# Schematic1.net
KiCad netlist of a schematic drawn in EasyEDA Pro
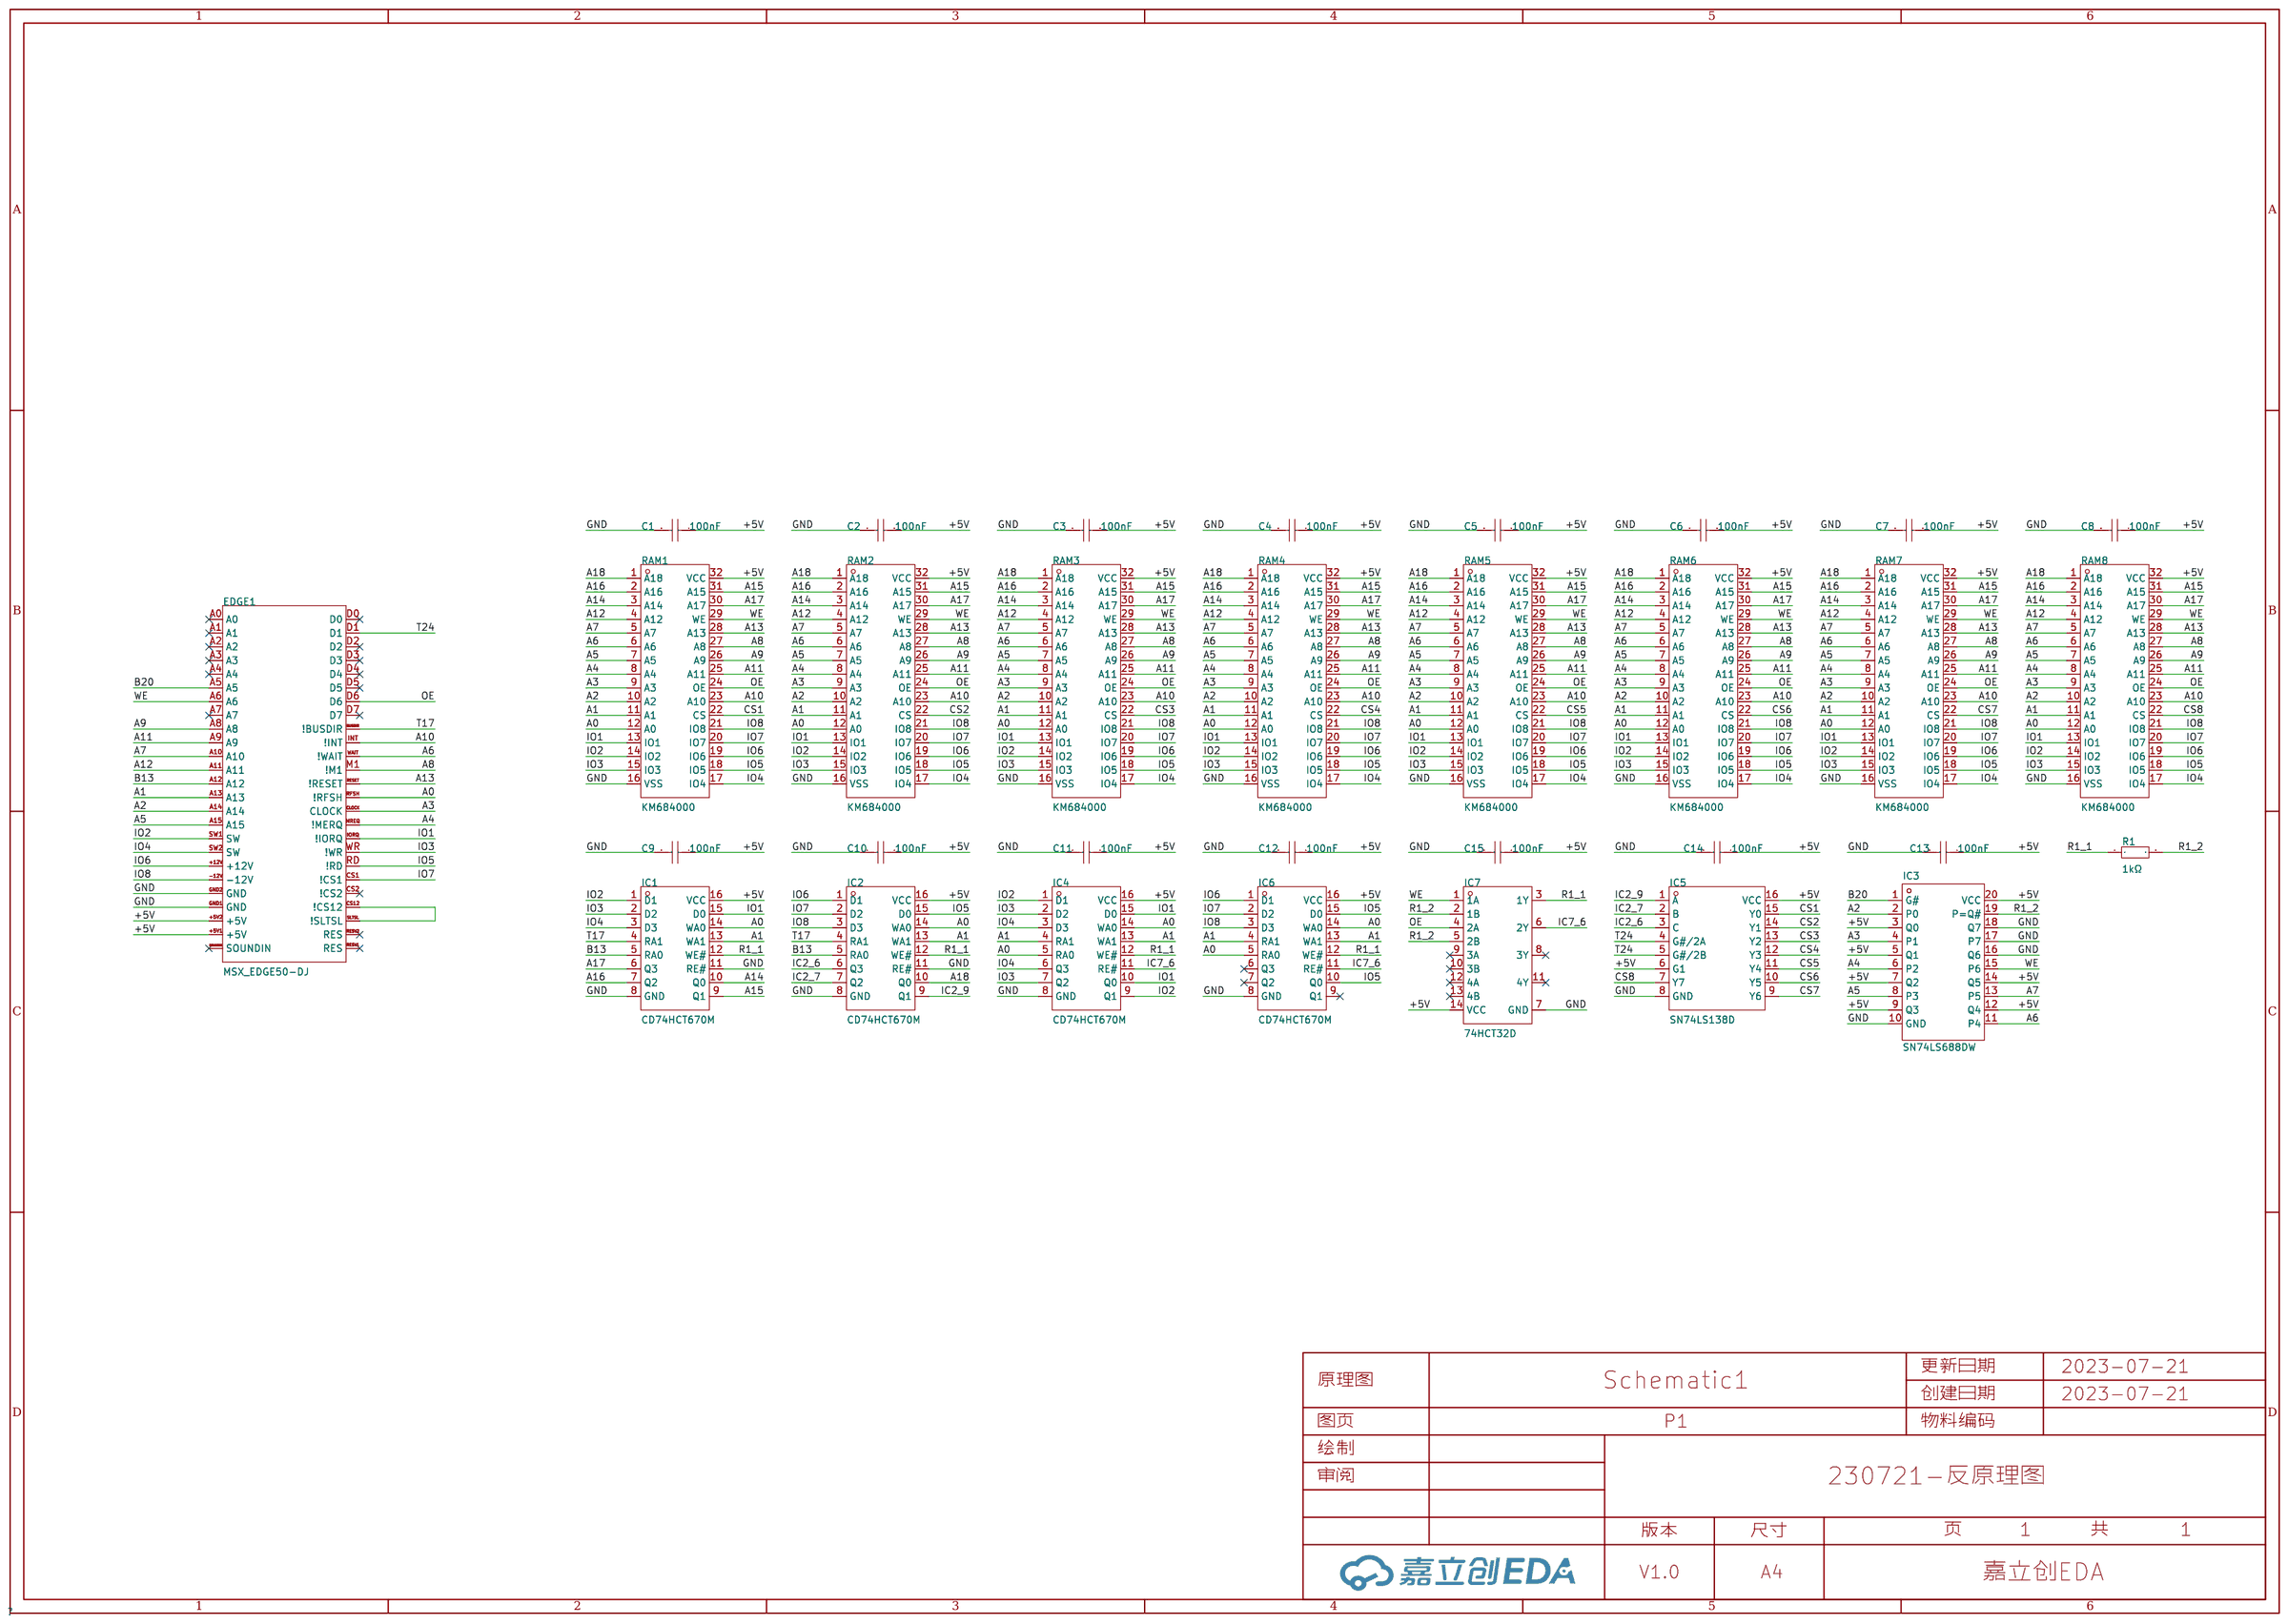
[diagram p0: schematic sheet]

(export (version "E")
  (design (tool "Eeschema 10.0.6"))
  (components
    (comp (ref "C1")
      (value "100nF")
      (footprint "easyedapro:C0805")
      (description "容值:100nF;精度:±10%;额定电压:50V;材质(温度系数):X7R;")
      (fields
        (field (name "Manufacturer Part") "CC0805KRX7R9BB104")
        (field (name "Manufacturer") "YAGEO(国巨)")
      )
      (libsource (lib "easyedapro") (part "CC0805KRX7R9BB104"))
    )
    (comp (ref "C2")
      (value "100nF")
      (footprint "easyedapro:C0805")
      (description "容值:100nF;精度:±10%;额定电压:50V;材质(温度系数):X7R;")
      (fields
        (field (name "Manufacturer Part") "CC0805KRX7R9BB104")
        (field (name "Manufacturer") "YAGEO(国巨)")
      )
      (libsource (lib "easyedapro") (part "CC0805KRX7R9BB104"))
    )
    (comp (ref "C3")
      (value "100nF")
      (footprint "easyedapro:C0805")
      (description "容值:100nF;精度:±10%;额定电压:50V;材质(温度系数):X7R;")
      (fields
        (field (name "Manufacturer Part") "CC0805KRX7R9BB104")
        (field (name "Manufacturer") "YAGEO(国巨)")
      )
      (libsource (lib "easyedapro") (part "CC0805KRX7R9BB104"))
    )
    (comp (ref "C4")
      (value "100nF")
      (footprint "easyedapro:C0805")
      (description "容值:100nF;精度:±10%;额定电压:50V;材质(温度系数):X7R;")
      (fields
        (field (name "Manufacturer Part") "CC0805KRX7R9BB104")
        (field (name "Manufacturer") "YAGEO(国巨)")
      )
      (libsource (lib "easyedapro") (part "CC0805KRX7R9BB104"))
    )
    (comp (ref "C5")
      (value "100nF")
      (footprint "easyedapro:C0805")
      (description "容值:100nF;精度:±10%;额定电压:50V;材质(温度系数):X7R;")
      (fields
        (field (name "Manufacturer Part") "CC0805KRX7R9BB104")
        (field (name "Manufacturer") "YAGEO(国巨)")
      )
      (libsource (lib "easyedapro") (part "CC0805KRX7R9BB104"))
    )
    (comp (ref "C6")
      (value "100nF")
      (footprint "easyedapro:C0805")
      (description "容值:100nF;精度:±10%;额定电压:50V;材质(温度系数):X7R;")
      (fields
        (field (name "Manufacturer Part") "CC0805KRX7R9BB104")
        (field (name "Manufacturer") "YAGEO(国巨)")
      )
      (libsource (lib "easyedapro") (part "CC0805KRX7R9BB104"))
    )
    (comp (ref "C7")
      (value "100nF")
      (footprint "easyedapro:C0805")
      (description "容值:100nF;精度:±10%;额定电压:50V;材质(温度系数):X7R;")
      (fields
        (field (name "Manufacturer Part") "CC0805KRX7R9BB104")
        (field (name "Manufacturer") "YAGEO(国巨)")
      )
      (libsource (lib "easyedapro") (part "CC0805KRX7R9BB104"))
    )
    (comp (ref "C8")
      (value "100nF")
      (footprint "easyedapro:C0805")
      (description "容值:100nF;精度:±10%;额定电压:50V;材质(温度系数):X7R;")
      (fields
        (field (name "Manufacturer Part") "CC0805KRX7R9BB104")
        (field (name "Manufacturer") "YAGEO(国巨)")
      )
      (libsource (lib "easyedapro") (part "CC0805KRX7R9BB104"))
    )
    (comp (ref "C9")
      (value "100nF")
      (footprint "easyedapro:C0805")
      (description "容值:100nF;精度:±10%;额定电压:50V;材质(温度系数):X7R;")
      (fields
        (field (name "Manufacturer Part") "CC0805KRX7R9BB104")
        (field (name "Manufacturer") "YAGEO(国巨)")
      )
      (libsource (lib "easyedapro") (part "CC0805KRX7R9BB104"))
    )
    (comp (ref "C10")
      (value "100nF")
      (footprint "easyedapro:C0805")
      (description "容值:100nF;精度:±10%;额定电压:50V;材质(温度系数):X7R;")
      (fields
        (field (name "Manufacturer Part") "CC0805KRX7R9BB104")
        (field (name "Manufacturer") "YAGEO(国巨)")
      )
      (libsource (lib "easyedapro") (part "CC0805KRX7R9BB104"))
    )
    (comp (ref "C11")
      (value "100nF")
      (footprint "easyedapro:C0805")
      (description "容值:100nF;精度:±10%;额定电压:50V;材质(温度系数):X7R;")
      (fields
        (field (name "Manufacturer Part") "CC0805KRX7R9BB104")
        (field (name "Manufacturer") "YAGEO(国巨)")
      )
      (libsource (lib "easyedapro") (part "CC0805KRX7R9BB104"))
    )
    (comp (ref "C12")
      (value "100nF")
      (footprint "easyedapro:C0805")
      (description "容值:100nF;精度:±10%;额定电压:50V;材质(温度系数):X7R;")
      (fields
        (field (name "Manufacturer Part") "CC0805KRX7R9BB104")
        (field (name "Manufacturer") "YAGEO(国巨)")
      )
      (libsource (lib "easyedapro") (part "CC0805KRX7R9BB104"))
    )
    (comp (ref "C13")
      (value "100nF")
      (footprint "easyedapro:C0805")
      (description "容值:100nF;精度:±10%;额定电压:50V;材质(温度系数):X7R;")
      (fields
        (field (name "Manufacturer Part") "CC0805KRX7R9BB104")
        (field (name "Manufacturer") "YAGEO(国巨)")
      )
      (libsource (lib "easyedapro") (part "CC0805KRX7R9BB104"))
    )
    (comp (ref "C14")
      (value "100nF")
      (footprint "easyedapro:C0805")
      (description "容值:100nF;精度:±10%;额定电压:50V;材质(温度系数):X7R;")
      (fields
        (field (name "Manufacturer Part") "CC0805KRX7R9BB104")
        (field (name "Manufacturer") "YAGEO(国巨)")
      )
      (libsource (lib "easyedapro") (part "CC0805KRX7R9BB104"))
    )
    (comp (ref "C15")
      (value "100nF")
      (footprint "easyedapro:C0805")
      (description "容值:100nF;精度:±10%;额定电压:50V;材质(温度系数):X7R;")
      (fields
        (field (name "Manufacturer Part") "CC0805KRX7R9BB104")
        (field (name "Manufacturer") "YAGEO(国巨)")
      )
      (libsource (lib "easyedapro") (part "CC0805KRX7R9BB104"))
    )
    (comp (ref "EDGE1")
      (value "MSX_EDGE50-DJ")
      (footprint "easyedapro:MSXCART_DJ")
      (libsource (lib "easyedapro") (part "MSX_EDGE50-DJ"))
    )
    (comp (ref "IC1")
      (value "CD74HCT670M")
      (footprint "easyedapro:SOIC-16_L9.9-W3.9-P1.27-LS6.0-BL")
      (description "高速 CMOS 逻辑 4 x 4 寄存器文件 16-SOIC -55 to 125")
      (fields (field (name "Manufacturer") "TI(德州仪器)"))
      (libsource (lib "easyedapro") (part "CD74HCT670M"))
    )
    (comp (ref "IC2")
      (value "CD74HCT670M")
      (footprint "easyedapro:SOIC-16_L9.9-W3.9-P1.27-LS6.0-BL")
      (description "高速 CMOS 逻辑 4 x 4 寄存器文件 16-SOIC -55 to 125")
      (fields (field (name "Manufacturer") "TI(德州仪器)"))
      (libsource (lib "easyedapro") (part "CD74HCT670M"))
    )
    (comp (ref "IC3")
      (value "SN74LS688DW")
      (footprint "easyedapro:SOIC-20_L12.8-W7.5-P1.27-LS10.3-BL")
      (description "具有使能端的 8 位等值/幅度比较器 (P=Q) 20-SOIC 0 to 70")
      (fields (field (name "Manufacturer") "TI(德州仪器)"))
      (libsource (lib "easyedapro") (part "SN74LS688DW"))
    )
    (comp (ref "IC4")
      (value "CD74HCT670M")
      (footprint "easyedapro:SOIC-16_L9.9-W3.9-P1.27-LS6.0-BL")
      (description "高速 CMOS 逻辑 4 x 4 寄存器文件 16-SOIC -55 to 125")
      (fields (field (name "Manufacturer") "TI(德州仪器)"))
      (libsource (lib "easyedapro") (part "CD74HCT670M"))
    )
    (comp (ref "IC5")
      (value "SN74LS138D")
      (footprint "easyedapro:SOIC-16_L9.9-W3.9-P1.27-LS6.0-BL")
      (description "类型:解码器/多路解器;低电平输出电流(IOL):8mA;高电平输出电流(IOH):400uA;供电电源:单电源;供电电压:4.75V~5.25V;工作温度:0°C~+70°C;")
      (fields (field (name "Manufacturer") "TI(德州仪器)"))
      (libsource (lib "easyedapro") (part "SN74LS138D"))
    )
    (comp (ref "IC6")
      (value "CD74HCT670M")
      (footprint "easyedapro:SOIC-16_L9.9-W3.9-P1.27-LS6.0-BL")
      (description "高速 CMOS 逻辑 4 x 4 寄存器文件 16-SOIC -55 to 125")
      (fields (field (name "Manufacturer") "TI(德州仪器)"))
      (libsource (lib "easyedapro") (part "CD74HCT670M"))
    )
    (comp (ref "IC7")
      (value "74HCT32D")
      (footprint "easyedapro:SOIC-14_L8.6-W3.9-P1.27-LS6.0-BL")
      (description "逻辑类型:或门;通道数:4;电源电压:4.5V~5.5V;静态电流(最大值):1uA;最大传播延迟:18ns@5.5V,50pF;")
      (fields (field (name "Manufacturer") "TOSHIBA(东芝)"))
      (libsource (lib "easyedapro") (part "74HCT32D"))
    )
    (comp (ref "R1")
      (value "1kΩ")
      (footprint "easyedapro:R0805")
      (description "电阻类型:厚膜电阻;阻值:1kΩ;精度:±1%;功率:125mW;")
      (fields
        (field (name "Manufacturer Part") "0805W8F1001T5E")
        (field (name "Manufacturer") "UNI-ROYAL(厚声)")
      )
      (libsource (lib "easyedapro") (part "0805W8F1001T5E"))
    )
    (comp (ref "RAM1")
      (value "KM684000")
      (footprint "easyedapro:SOP-32_L20.9-W11.4-P1.27-LS14.12-BL")
      (description "存储器类型:-;存储器容量:-;存储器接口类型:-;工作电压:-;")
      (libsource (lib "easyedapro") (part "KM684000"))
    )
    (comp (ref "RAM2")
      (value "KM684000")
      (footprint "easyedapro:SOP-32_L20.9-W11.4-P1.27-LS14.12-BL")
      (description "存储器类型:-;存储器容量:-;存储器接口类型:-;工作电压:-;")
      (libsource (lib "easyedapro") (part "KM684000"))
    )
    (comp (ref "RAM3")
      (value "KM684000")
      (footprint "easyedapro:SOP-32_L20.9-W11.4-P1.27-LS14.12-BL")
      (description "存储器类型:-;存储器容量:-;存储器接口类型:-;工作电压:-;")
      (libsource (lib "easyedapro") (part "KM684000"))
    )
    (comp (ref "RAM4")
      (value "KM684000")
      (footprint "easyedapro:SOP-32_L20.9-W11.4-P1.27-LS14.12-BL")
      (description "存储器类型:-;存储器容量:-;存储器接口类型:-;工作电压:-;")
      (libsource (lib "easyedapro") (part "KM684000"))
    )
    (comp (ref "RAM5")
      (value "KM684000")
      (footprint "easyedapro:SOP-32_L20.9-W11.4-P1.27-LS14.12-BL")
      (description "存储器类型:-;存储器容量:-;存储器接口类型:-;工作电压:-;")
      (libsource (lib "easyedapro") (part "KM684000"))
    )
    (comp (ref "RAM6")
      (value "KM684000")
      (footprint "easyedapro:SOP-32_L20.9-W11.4-P1.27-LS14.12-BL")
      (description "存储器类型:-;存储器容量:-;存储器接口类型:-;工作电压:-;")
      (libsource (lib "easyedapro") (part "KM684000"))
    )
    (comp (ref "RAM7")
      (value "KM684000")
      (footprint "easyedapro:SOP-32_L20.9-W11.4-P1.27-LS14.12-BL")
      (description "存储器类型:-;存储器容量:-;存储器接口类型:-;工作电压:-;")
      (libsource (lib "easyedapro") (part "KM684000"))
    )
    (comp (ref "RAM8")
      (value "KM684000")
      (footprint "easyedapro:SOP-32_L20.9-W11.4-P1.27-LS14.12-BL")
      (description "存储器类型:-;存储器容量:-;存储器接口类型:-;工作电压:-;")
      (libsource (lib "easyedapro") (part "KM684000"))
    )
  )
  (nets
    (net (code "1") (name "/+5V") (class "Default")
      (node (ref "C1") (pin "1") (pinfunction "1_1") (pintype "input"))
      (node (ref "C10") (pin "1") (pinfunction "1_1") (pintype "input"))
      (node (ref "C11") (pin "1") (pinfunction "1_1") (pintype "input"))
      (node (ref "C12") (pin "1") (pinfunction "1_1") (pintype "input"))
      (node (ref "C13") (pin "1") (pinfunction "1_1") (pintype "input"))
      (node (ref "C14") (pin "1") (pinfunction "1_1") (pintype "input"))
      (node (ref "C15") (pin "1") (pinfunction "1_1") (pintype "input"))
      (node (ref "C2") (pin "1") (pinfunction "1_1") (pintype "input"))
      (node (ref "C3") (pin "1") (pinfunction "1_1") (pintype "input"))
      (node (ref "C4") (pin "1") (pinfunction "1_1") (pintype "input"))
      (node (ref "C5") (pin "1") (pinfunction "1_1") (pintype "input"))
      (node (ref "C6") (pin "1") (pinfunction "1_1") (pintype "input"))
      (node (ref "C7") (pin "1") (pinfunction "1_1") (pintype "input"))
      (node (ref "C8") (pin "1") (pinfunction "1_1") (pintype "input"))
      (node (ref "C9") (pin "1") (pinfunction "1_1") (pintype "input"))
      (node (ref "EDGE1") (pin "+5V1") (pinfunction "+5V_+5V1") (pintype "input"))
      (node (ref "EDGE1") (pin "+5V2") (pinfunction "+5V_+5V2") (pintype "input"))
      (node (ref "IC1") (pin "16") (pinfunction "VCC_16") (pintype "input"))
      (node (ref "IC2") (pin "16") (pinfunction "VCC_16") (pintype "input"))
      (node (ref "IC3") (pin "12") (pinfunction "Q4_12") (pintype "input"))
      (node (ref "IC3") (pin "14") (pinfunction "Q5_14") (pintype "input"))
      (node (ref "IC3") (pin "20") (pinfunction "VCC_20") (pintype "input"))
      (node (ref "IC3") (pin "3") (pinfunction "Q0_3") (pintype "input"))
      (node (ref "IC3") (pin "5") (pinfunction "Q1_5") (pintype "input"))
      (node (ref "IC3") (pin "7") (pinfunction "Q2_7") (pintype "input"))
      (node (ref "IC3") (pin "9") (pinfunction "Q3_9") (pintype "input"))
      (node (ref "IC4") (pin "16") (pinfunction "VCC_16") (pintype "input"))
      (node (ref "IC5") (pin "16") (pinfunction "VCC_16") (pintype "input"))
      (node (ref "IC5") (pin "6") (pinfunction "G1_6") (pintype "input"))
      (node (ref "IC6") (pin "16") (pinfunction "VCC_16") (pintype "input"))
      (node (ref "IC7") (pin "14") (pinfunction "VCC_14") (pintype "input"))
      (node (ref "RAM1") (pin "32") (pinfunction "VCC_32") (pintype "input"))
      (node (ref "RAM2") (pin "32") (pinfunction "VCC_32") (pintype "input"))
      (node (ref "RAM3") (pin "32") (pinfunction "VCC_32") (pintype "input"))
      (node (ref "RAM4") (pin "32") (pinfunction "VCC_32") (pintype "input"))
      (node (ref "RAM5") (pin "32") (pinfunction "VCC_32") (pintype "input"))
      (node (ref "RAM6") (pin "32") (pinfunction "VCC_32") (pintype "input"))
      (node (ref "RAM7") (pin "32") (pinfunction "VCC_32") (pintype "input"))
      (node (ref "RAM8") (pin "32") (pinfunction "VCC_32") (pintype "input"))
    )
    (net (code "2") (name "/A0") (class "Default")
      (node (ref "EDGE1") (pin "RFSH") (pinfunction "!RFSH_RFSH") (pintype "output"))
      (node (ref "IC1") (pin "14") (pinfunction "WA0_14") (pintype "input"))
      (node (ref "IC2") (pin "14") (pinfunction "WA0_14") (pintype "input"))
      (node (ref "IC4") (pin "14") (pinfunction "WA0_14") (pintype "input"))
      (node (ref "IC4") (pin "5") (pinfunction "RA0_5") (pintype "input"))
      (node (ref "IC6") (pin "14") (pinfunction "WA0_14") (pintype "input"))
      (node (ref "IC6") (pin "5") (pinfunction "RA0_5") (pintype "input"))
      (node (ref "RAM1") (pin "12") (pinfunction "A0_12") (pintype "input"))
      (node (ref "RAM2") (pin "12") (pinfunction "A0_12") (pintype "input"))
      (node (ref "RAM3") (pin "12") (pinfunction "A0_12") (pintype "input"))
      (node (ref "RAM4") (pin "12") (pinfunction "A0_12") (pintype "input"))
      (node (ref "RAM5") (pin "12") (pinfunction "A0_12") (pintype "input"))
      (node (ref "RAM6") (pin "12") (pinfunction "A0_12") (pintype "input"))
      (node (ref "RAM7") (pin "12") (pinfunction "A0_12") (pintype "input"))
      (node (ref "RAM8") (pin "12") (pinfunction "A0_12") (pintype "input"))
    )
    (net (code "3") (name "/A1") (class "Default")
      (node (ref "EDGE1") (pin "A13") (pinfunction "A13_A13") (pintype "output"))
      (node (ref "IC1") (pin "13") (pinfunction "WA1_13") (pintype "input"))
      (node (ref "IC2") (pin "13") (pinfunction "WA1_13") (pintype "input"))
      (node (ref "IC4") (pin "13") (pinfunction "WA1_13") (pintype "input"))
      (node (ref "IC4") (pin "4") (pinfunction "RA1_4") (pintype "input"))
      (node (ref "IC6") (pin "13") (pinfunction "WA1_13") (pintype "input"))
      (node (ref "IC6") (pin "4") (pinfunction "RA1_4") (pintype "input"))
      (node (ref "RAM1") (pin "11") (pinfunction "A1_11") (pintype "input"))
      (node (ref "RAM2") (pin "11") (pinfunction "A1_11") (pintype "input"))
      (node (ref "RAM3") (pin "11") (pinfunction "A1_11") (pintype "input"))
      (node (ref "RAM4") (pin "11") (pinfunction "A1_11") (pintype "input"))
      (node (ref "RAM5") (pin "11") (pinfunction "A1_11") (pintype "input"))
      (node (ref "RAM6") (pin "11") (pinfunction "A1_11") (pintype "input"))
      (node (ref "RAM7") (pin "11") (pinfunction "A1_11") (pintype "input"))
      (node (ref "RAM8") (pin "11") (pinfunction "A1_11") (pintype "input"))
    )
    (net (code "4") (name "/A2") (class "Default")
      (node (ref "EDGE1") (pin "A14") (pinfunction "A14_A14") (pintype "output"))
      (node (ref "IC3") (pin "2") (pinfunction "P0_2") (pintype "input"))
      (node (ref "RAM1") (pin "10") (pinfunction "A2_10") (pintype "input"))
      (node (ref "RAM2") (pin "10") (pinfunction "A2_10") (pintype "input"))
      (node (ref "RAM3") (pin "10") (pinfunction "A2_10") (pintype "input"))
      (node (ref "RAM4") (pin "10") (pinfunction "A2_10") (pintype "input"))
      (node (ref "RAM5") (pin "10") (pinfunction "A2_10") (pintype "input"))
      (node (ref "RAM6") (pin "10") (pinfunction "A2_10") (pintype "input"))
      (node (ref "RAM7") (pin "10") (pinfunction "A2_10") (pintype "input"))
      (node (ref "RAM8") (pin "10") (pinfunction "A2_10") (pintype "input"))
    )
    (net (code "5") (name "/A3") (class "Default")
      (node (ref "EDGE1") (pin "CLOCK") (pinfunction "CLOCK_CLOCK") (pintype "output"))
      (node (ref "IC3") (pin "4") (pinfunction "P1_4") (pintype "input"))
      (node (ref "RAM1") (pin "9") (pinfunction "A3_9") (pintype "input"))
      (node (ref "RAM2") (pin "9") (pinfunction "A3_9") (pintype "input"))
      (node (ref "RAM3") (pin "9") (pinfunction "A3_9") (pintype "input"))
      (node (ref "RAM4") (pin "9") (pinfunction "A3_9") (pintype "input"))
      (node (ref "RAM5") (pin "9") (pinfunction "A3_9") (pintype "input"))
      (node (ref "RAM6") (pin "9") (pinfunction "A3_9") (pintype "input"))
      (node (ref "RAM7") (pin "9") (pinfunction "A3_9") (pintype "input"))
      (node (ref "RAM8") (pin "9") (pinfunction "A3_9") (pintype "input"))
    )
    (net (code "6") (name "/A4") (class "Default")
      (node (ref "EDGE1") (pin "MREQ") (pinfunction "!MERQ_MREQ") (pintype "output"))
      (node (ref "IC3") (pin "6") (pinfunction "P2_6") (pintype "input"))
      (node (ref "RAM1") (pin "8") (pinfunction "A4_8") (pintype "input"))
      (node (ref "RAM2") (pin "8") (pinfunction "A4_8") (pintype "input"))
      (node (ref "RAM3") (pin "8") (pinfunction "A4_8") (pintype "input"))
      (node (ref "RAM4") (pin "8") (pinfunction "A4_8") (pintype "input"))
      (node (ref "RAM5") (pin "8") (pinfunction "A4_8") (pintype "input"))
      (node (ref "RAM6") (pin "8") (pinfunction "A4_8") (pintype "input"))
      (node (ref "RAM7") (pin "8") (pinfunction "A4_8") (pintype "input"))
      (node (ref "RAM8") (pin "8") (pinfunction "A4_8") (pintype "input"))
    )
    (net (code "7") (name "/A5") (class "Default")
      (node (ref "EDGE1") (pin "A15") (pinfunction "A15_A15") (pintype "output"))
      (node (ref "IC3") (pin "8") (pinfunction "P3_8") (pintype "input"))
      (node (ref "RAM1") (pin "7") (pinfunction "A5_7") (pintype "input"))
      (node (ref "RAM2") (pin "7") (pinfunction "A5_7") (pintype "input"))
      (node (ref "RAM3") (pin "7") (pinfunction "A5_7") (pintype "input"))
      (node (ref "RAM4") (pin "7") (pinfunction "A5_7") (pintype "input"))
      (node (ref "RAM5") (pin "7") (pinfunction "A5_7") (pintype "input"))
      (node (ref "RAM6") (pin "7") (pinfunction "A5_7") (pintype "input"))
      (node (ref "RAM7") (pin "7") (pinfunction "A5_7") (pintype "input"))
      (node (ref "RAM8") (pin "7") (pinfunction "A5_7") (pintype "input"))
    )
    (net (code "8") (name "/A6") (class "Default")
      (node (ref "EDGE1") (pin "WAIT") (pinfunction "!WAIT_WAIT") (pintype "input"))
      (node (ref "IC3") (pin "11") (pinfunction "P4_11") (pintype "input"))
      (node (ref "RAM1") (pin "6") (pinfunction "A6_6") (pintype "input"))
      (node (ref "RAM2") (pin "6") (pinfunction "A6_6") (pintype "input"))
      (node (ref "RAM3") (pin "6") (pinfunction "A6_6") (pintype "input"))
      (node (ref "RAM4") (pin "6") (pinfunction "A6_6") (pintype "input"))
      (node (ref "RAM5") (pin "6") (pinfunction "A6_6") (pintype "input"))
      (node (ref "RAM6") (pin "6") (pinfunction "A6_6") (pintype "input"))
      (node (ref "RAM7") (pin "6") (pinfunction "A6_6") (pintype "input"))
      (node (ref "RAM8") (pin "6") (pinfunction "A6_6") (pintype "input"))
    )
    (net (code "9") (name "/A7") (class "Default")
      (node (ref "EDGE1") (pin "A10") (pinfunction "A10_A10") (pintype "output"))
      (node (ref "IC3") (pin "13") (pinfunction "P5_13") (pintype "input"))
      (node (ref "RAM1") (pin "5") (pinfunction "A7_5") (pintype "input"))
      (node (ref "RAM2") (pin "5") (pinfunction "A7_5") (pintype "input"))
      (node (ref "RAM3") (pin "5") (pinfunction "A7_5") (pintype "input"))
      (node (ref "RAM4") (pin "5") (pinfunction "A7_5") (pintype "input"))
      (node (ref "RAM5") (pin "5") (pinfunction "A7_5") (pintype "input"))
      (node (ref "RAM6") (pin "5") (pinfunction "A7_5") (pintype "input"))
      (node (ref "RAM7") (pin "5") (pinfunction "A7_5") (pintype "input"))
      (node (ref "RAM8") (pin "5") (pinfunction "A7_5") (pintype "input"))
    )
    (net (code "10") (name "/A8") (class "Default")
      (node (ref "EDGE1") (pin "M1") (pinfunction "!M1_M1") (pintype "output"))
      (node (ref "RAM1") (pin "27") (pinfunction "A8_27") (pintype "input"))
      (node (ref "RAM2") (pin "27") (pinfunction "A8_27") (pintype "input"))
      (node (ref "RAM3") (pin "27") (pinfunction "A8_27") (pintype "input"))
      (node (ref "RAM4") (pin "27") (pinfunction "A8_27") (pintype "input"))
      (node (ref "RAM5") (pin "27") (pinfunction "A8_27") (pintype "input"))
      (node (ref "RAM6") (pin "27") (pinfunction "A8_27") (pintype "input"))
      (node (ref "RAM7") (pin "27") (pinfunction "A8_27") (pintype "input"))
      (node (ref "RAM8") (pin "27") (pinfunction "A8_27") (pintype "input"))
    )
    (net (code "11") (name "/A9") (class "Default")
      (node (ref "EDGE1") (pin "A8") (pinfunction "A8_A8") (pintype "output"))
      (node (ref "RAM1") (pin "26") (pinfunction "A9_26") (pintype "input"))
      (node (ref "RAM2") (pin "26") (pinfunction "A9_26") (pintype "input"))
      (node (ref "RAM3") (pin "26") (pinfunction "A9_26") (pintype "input"))
      (node (ref "RAM4") (pin "26") (pinfunction "A9_26") (pintype "input"))
      (node (ref "RAM5") (pin "26") (pinfunction "A9_26") (pintype "input"))
      (node (ref "RAM6") (pin "26") (pinfunction "A9_26") (pintype "input"))
      (node (ref "RAM7") (pin "26") (pinfunction "A9_26") (pintype "input"))
      (node (ref "RAM8") (pin "26") (pinfunction "A9_26") (pintype "input"))
    )
    (net (code "12") (name "/A10") (class "Default")
      (node (ref "EDGE1") (pin "INT") (pinfunction "!INT_INT") (pintype "input"))
      (node (ref "RAM1") (pin "23") (pinfunction "A10_23") (pintype "input"))
      (node (ref "RAM2") (pin "23") (pinfunction "A10_23") (pintype "input"))
      (node (ref "RAM3") (pin "23") (pinfunction "A10_23") (pintype "input"))
      (node (ref "RAM4") (pin "23") (pinfunction "A10_23") (pintype "input"))
      (node (ref "RAM5") (pin "23") (pinfunction "A10_23") (pintype "input"))
      (node (ref "RAM6") (pin "23") (pinfunction "A10_23") (pintype "input"))
      (node (ref "RAM7") (pin "23") (pinfunction "A10_23") (pintype "input"))
      (node (ref "RAM8") (pin "23") (pinfunction "A10_23") (pintype "input"))
    )
    (net (code "13") (name "/A11") (class "Default")
      (node (ref "EDGE1") (pin "A9") (pinfunction "A9_A9") (pintype "output"))
      (node (ref "RAM1") (pin "25") (pinfunction "A11_25") (pintype "input"))
      (node (ref "RAM2") (pin "25") (pinfunction "A11_25") (pintype "input"))
      (node (ref "RAM3") (pin "25") (pinfunction "A11_25") (pintype "input"))
      (node (ref "RAM4") (pin "25") (pinfunction "A11_25") (pintype "input"))
      (node (ref "RAM5") (pin "25") (pinfunction "A11_25") (pintype "input"))
      (node (ref "RAM6") (pin "25") (pinfunction "A11_25") (pintype "input"))
      (node (ref "RAM7") (pin "25") (pinfunction "A11_25") (pintype "input"))
      (node (ref "RAM8") (pin "25") (pinfunction "A11_25") (pintype "input"))
    )
    (net (code "14") (name "/A12") (class "Default")
      (node (ref "EDGE1") (pin "A11") (pinfunction "A11_A11") (pintype "output"))
      (node (ref "RAM1") (pin "4") (pinfunction "A12_4") (pintype "input"))
      (node (ref "RAM2") (pin "4") (pinfunction "A12_4") (pintype "input"))
      (node (ref "RAM3") (pin "4") (pinfunction "A12_4") (pintype "input"))
      (node (ref "RAM4") (pin "4") (pinfunction "A12_4") (pintype "input"))
      (node (ref "RAM5") (pin "4") (pinfunction "A12_4") (pintype "input"))
      (node (ref "RAM6") (pin "4") (pinfunction "A12_4") (pintype "input"))
      (node (ref "RAM7") (pin "4") (pinfunction "A12_4") (pintype "input"))
      (node (ref "RAM8") (pin "4") (pinfunction "A12_4") (pintype "input"))
    )
    (net (code "15") (name "/A13") (class "Default")
      (node (ref "EDGE1") (pin "RESET") (pinfunction "!RESET_RESET") (pintype "output"))
      (node (ref "RAM1") (pin "28") (pinfunction "A13_28") (pintype "input"))
      (node (ref "RAM2") (pin "28") (pinfunction "A13_28") (pintype "input"))
      (node (ref "RAM3") (pin "28") (pinfunction "A13_28") (pintype "input"))
      (node (ref "RAM4") (pin "28") (pinfunction "A13_28") (pintype "input"))
      (node (ref "RAM5") (pin "28") (pinfunction "A13_28") (pintype "input"))
      (node (ref "RAM6") (pin "28") (pinfunction "A13_28") (pintype "input"))
      (node (ref "RAM7") (pin "28") (pinfunction "A13_28") (pintype "input"))
      (node (ref "RAM8") (pin "28") (pinfunction "A13_28") (pintype "input"))
    )
    (net (code "16") (name "/A14") (class "Default")
      (node (ref "IC1") (pin "10") (pinfunction "Q0_10") (pintype "input"))
      (node (ref "RAM1") (pin "3") (pinfunction "A14_3") (pintype "input"))
      (node (ref "RAM2") (pin "3") (pinfunction "A14_3") (pintype "input"))
      (node (ref "RAM3") (pin "3") (pinfunction "A14_3") (pintype "input"))
      (node (ref "RAM4") (pin "3") (pinfunction "A14_3") (pintype "input"))
      (node (ref "RAM5") (pin "3") (pinfunction "A14_3") (pintype "input"))
      (node (ref "RAM6") (pin "3") (pinfunction "A14_3") (pintype "input"))
      (node (ref "RAM7") (pin "3") (pinfunction "A14_3") (pintype "input"))
      (node (ref "RAM8") (pin "3") (pinfunction "A14_3") (pintype "input"))
    )
    (net (code "17") (name "/A15") (class "Default")
      (node (ref "IC1") (pin "9") (pinfunction "Q1_9") (pintype "input"))
      (node (ref "RAM1") (pin "31") (pinfunction "A15_31") (pintype "input"))
      (node (ref "RAM2") (pin "31") (pinfunction "A15_31") (pintype "input"))
      (node (ref "RAM3") (pin "31") (pinfunction "A15_31") (pintype "input"))
      (node (ref "RAM4") (pin "31") (pinfunction "A15_31") (pintype "input"))
      (node (ref "RAM5") (pin "31") (pinfunction "A15_31") (pintype "input"))
      (node (ref "RAM6") (pin "31") (pinfunction "A15_31") (pintype "input"))
      (node (ref "RAM7") (pin "31") (pinfunction "A15_31") (pintype "input"))
      (node (ref "RAM8") (pin "31") (pinfunction "A15_31") (pintype "input"))
    )
    (net (code "18") (name "/A16") (class "Default")
      (node (ref "IC1") (pin "7") (pinfunction "Q2_7") (pintype "input"))
      (node (ref "RAM1") (pin "2") (pinfunction "A16_2") (pintype "input"))
      (node (ref "RAM2") (pin "2") (pinfunction "A16_2") (pintype "input"))
      (node (ref "RAM3") (pin "2") (pinfunction "A16_2") (pintype "input"))
      (node (ref "RAM4") (pin "2") (pinfunction "A16_2") (pintype "input"))
      (node (ref "RAM5") (pin "2") (pinfunction "A16_2") (pintype "input"))
      (node (ref "RAM6") (pin "2") (pinfunction "A16_2") (pintype "input"))
      (node (ref "RAM7") (pin "2") (pinfunction "A16_2") (pintype "input"))
      (node (ref "RAM8") (pin "2") (pinfunction "A16_2") (pintype "input"))
    )
    (net (code "19") (name "/A17") (class "Default")
      (node (ref "IC1") (pin "6") (pinfunction "Q3_6") (pintype "input"))
      (node (ref "RAM1") (pin "30") (pinfunction "A17_30") (pintype "input"))
      (node (ref "RAM2") (pin "30") (pinfunction "A17_30") (pintype "input"))
      (node (ref "RAM3") (pin "30") (pinfunction "A17_30") (pintype "input"))
      (node (ref "RAM4") (pin "30") (pinfunction "A17_30") (pintype "input"))
      (node (ref "RAM5") (pin "30") (pinfunction "A17_30") (pintype "input"))
      (node (ref "RAM6") (pin "30") (pinfunction "A17_30") (pintype "input"))
      (node (ref "RAM7") (pin "30") (pinfunction "A17_30") (pintype "input"))
      (node (ref "RAM8") (pin "30") (pinfunction "A17_30") (pintype "input"))
    )
    (net (code "20") (name "/A18") (class "Default")
      (node (ref "IC2") (pin "10") (pinfunction "Q0_10") (pintype "input"))
      (node (ref "RAM1") (pin "1") (pinfunction "A18_1") (pintype "input"))
      (node (ref "RAM2") (pin "1") (pinfunction "A18_1") (pintype "input"))
      (node (ref "RAM3") (pin "1") (pinfunction "A18_1") (pintype "input"))
      (node (ref "RAM4") (pin "1") (pinfunction "A18_1") (pintype "input"))
      (node (ref "RAM5") (pin "1") (pinfunction "A18_1") (pintype "input"))
      (node (ref "RAM6") (pin "1") (pinfunction "A18_1") (pintype "input"))
      (node (ref "RAM7") (pin "1") (pinfunction "A18_1") (pintype "input"))
      (node (ref "RAM8") (pin "1") (pinfunction "A18_1") (pintype "input"))
    )
    (net (code "21") (name "/B13") (class "Default")
      (node (ref "EDGE1") (pin "A12") (pinfunction "A12_A12") (pintype "output"))
      (node (ref "IC1") (pin "5") (pinfunction "RA0_5") (pintype "input"))
      (node (ref "IC2") (pin "5") (pinfunction "RA0_5") (pintype "input"))
    )
    (net (code "22") (name "/B20") (class "Default")
      (node (ref "EDGE1") (pin "A5") (pinfunction "A5_A5") (pintype "output"))
      (node (ref "IC3") (pin "1") (pinfunction "G#_1") (pintype "input"))
    )
    (net (code "23") (name "/CS1") (class "Default")
      (node (ref "IC5") (pin "15") (pinfunction "Y0_15") (pintype "input"))
      (node (ref "RAM1") (pin "22") (pinfunction "CS_22") (pintype "input"))
    )
    (net (code "24") (name "/CS2") (class "Default")
      (node (ref "IC5") (pin "14") (pinfunction "Y1_14") (pintype "input"))
      (node (ref "RAM2") (pin "22") (pinfunction "CS_22") (pintype "input"))
    )
    (net (code "25") (name "/CS3") (class "Default")
      (node (ref "IC5") (pin "13") (pinfunction "Y2_13") (pintype "input"))
      (node (ref "RAM3") (pin "22") (pinfunction "CS_22") (pintype "input"))
    )
    (net (code "26") (name "/CS4") (class "Default")
      (node (ref "IC5") (pin "12") (pinfunction "Y3_12") (pintype "input"))
      (node (ref "RAM4") (pin "22") (pinfunction "CS_22") (pintype "input"))
    )
    (net (code "27") (name "/CS5") (class "Default")
      (node (ref "IC5") (pin "11") (pinfunction "Y4_11") (pintype "input"))
      (node (ref "RAM5") (pin "22") (pinfunction "CS_22") (pintype "input"))
    )
    (net (code "28") (name "/CS6") (class "Default")
      (node (ref "IC5") (pin "10") (pinfunction "Y5_10") (pintype "input"))
      (node (ref "RAM6") (pin "22") (pinfunction "CS_22") (pintype "input"))
    )
    (net (code "29") (name "/CS7") (class "Default")
      (node (ref "IC5") (pin "9") (pinfunction "Y6_9") (pintype "input"))
      (node (ref "RAM7") (pin "22") (pinfunction "CS_22") (pintype "input"))
    )
    (net (code "30") (name "/CS8") (class "Default")
      (node (ref "IC5") (pin "7") (pinfunction "Y7_7") (pintype "input"))
      (node (ref "RAM8") (pin "22") (pinfunction "CS_22") (pintype "input"))
    )
    (net (code "31") (name "/GND") (class "Default")
      (node (ref "C1") (pin "2") (pinfunction "2_2") (pintype "input"))
      (node (ref "C10") (pin "2") (pinfunction "2_2") (pintype "input"))
      (node (ref "C11") (pin "2") (pinfunction "2_2") (pintype "input"))
      (node (ref "C12") (pin "2") (pinfunction "2_2") (pintype "input"))
      (node (ref "C13") (pin "2") (pinfunction "2_2") (pintype "input"))
      (node (ref "C14") (pin "2") (pinfunction "2_2") (pintype "input"))
      (node (ref "C15") (pin "2") (pinfunction "2_2") (pintype "input"))
      (node (ref "C2") (pin "2") (pinfunction "2_2") (pintype "input"))
      (node (ref "C3") (pin "2") (pinfunction "2_2") (pintype "input"))
      (node (ref "C4") (pin "2") (pinfunction "2_2") (pintype "input"))
      (node (ref "C5") (pin "2") (pinfunction "2_2") (pintype "input"))
      (node (ref "C6") (pin "2") (pinfunction "2_2") (pintype "input"))
      (node (ref "C7") (pin "2") (pinfunction "2_2") (pintype "input"))
      (node (ref "C8") (pin "2") (pinfunction "2_2") (pintype "input"))
      (node (ref "C9") (pin "2") (pinfunction "2_2") (pintype "input"))
      (node (ref "EDGE1") (pin "GND1") (pinfunction "GND_GND1") (pintype "input"))
      (node (ref "EDGE1") (pin "GND2") (pinfunction "GND_GND2") (pintype "input"))
      (node (ref "IC1") (pin "11") (pinfunction "RE#_11") (pintype "input"))
      (node (ref "IC1") (pin "8") (pinfunction "GND_8") (pintype "input"))
      (node (ref "IC2") (pin "11") (pinfunction "RE#_11") (pintype "input"))
      (node (ref "IC2") (pin "8") (pinfunction "GND_8") (pintype "input"))
      (node (ref "IC3") (pin "10") (pinfunction "GND_10") (pintype "input"))
      (node (ref "IC3") (pin "16") (pinfunction "Q6_16") (pintype "input"))
      (node (ref "IC3") (pin "17") (pinfunction "P7_17") (pintype "input"))
      (node (ref "IC3") (pin "18") (pinfunction "Q7_18") (pintype "input"))
      (node (ref "IC4") (pin "8") (pinfunction "GND_8") (pintype "input"))
      (node (ref "IC5") (pin "8") (pinfunction "GND_8") (pintype "input"))
      (node (ref "IC6") (pin "8") (pinfunction "GND_8") (pintype "input"))
      (node (ref "IC7") (pin "7") (pinfunction "GND_7") (pintype "input"))
      (node (ref "RAM1") (pin "16") (pinfunction "VSS_16") (pintype "input"))
      (node (ref "RAM2") (pin "16") (pinfunction "VSS_16") (pintype "input"))
      (node (ref "RAM3") (pin "16") (pinfunction "VSS_16") (pintype "input"))
      (node (ref "RAM4") (pin "16") (pinfunction "VSS_16") (pintype "input"))
      (node (ref "RAM5") (pin "16") (pinfunction "VSS_16") (pintype "input"))
      (node (ref "RAM6") (pin "16") (pinfunction "VSS_16") (pintype "input"))
      (node (ref "RAM7") (pin "16") (pinfunction "VSS_16") (pintype "input"))
      (node (ref "RAM8") (pin "16") (pinfunction "VSS_16") (pintype "input"))
    )
    (net (code "32") (name "/IC2_6") (class "Default")
      (node (ref "IC2") (pin "6") (pinfunction "Q3_6") (pintype "input"))
      (node (ref "IC5") (pin "3") (pinfunction "C_3") (pintype "input"))
    )
    (net (code "33") (name "/IC2_7") (class "Default")
      (node (ref "IC2") (pin "7") (pinfunction "Q2_7") (pintype "input"))
      (node (ref "IC5") (pin "2") (pinfunction "B_2") (pintype "input"))
    )
    (net (code "34") (name "/IC2_9") (class "Default")
      (node (ref "IC2") (pin "9") (pinfunction "Q1_9") (pintype "input"))
      (node (ref "IC5") (pin "1") (pinfunction "A_1") (pintype "input"))
    )
    (net (code "35") (name "/IC7_6") (class "Default")
      (node (ref "IC4") (pin "11") (pinfunction "RE#_11") (pintype "input"))
      (node (ref "IC6") (pin "11") (pinfunction "RE#_11") (pintype "input"))
      (node (ref "IC7") (pin "6") (pinfunction "2Y_6") (pintype "input"))
    )
    (net (code "36") (name "/IO1") (class "Default")
      (node (ref "EDGE1") (pin "IORQ") (pinfunction "!IORQ_IORQ") (pintype "output"))
      (node (ref "IC1") (pin "15") (pinfunction "D0_15") (pintype "input"))
      (node (ref "IC4") (pin "10") (pinfunction "Q0_10") (pintype "input"))
      (node (ref "IC4") (pin "15") (pinfunction "D0_15") (pintype "input"))
      (node (ref "RAM1") (pin "13") (pinfunction "IO1_13") (pintype "input"))
      (node (ref "RAM2") (pin "13") (pinfunction "IO1_13") (pintype "input"))
      (node (ref "RAM3") (pin "13") (pinfunction "IO1_13") (pintype "input"))
      (node (ref "RAM4") (pin "13") (pinfunction "IO1_13") (pintype "input"))
      (node (ref "RAM5") (pin "13") (pinfunction "IO1_13") (pintype "input"))
      (node (ref "RAM6") (pin "13") (pinfunction "IO1_13") (pintype "input"))
      (node (ref "RAM7") (pin "13") (pinfunction "IO1_13") (pintype "input"))
      (node (ref "RAM8") (pin "13") (pinfunction "IO1_13") (pintype "input"))
    )
    (net (code "37") (name "/IO2") (class "Default")
      (node (ref "EDGE1") (pin "SW1") (pinfunction "SW_SW1") (pintype "input"))
      (node (ref "IC1") (pin "1") (pinfunction "D1_1") (pintype "input"))
      (node (ref "IC4") (pin "1") (pinfunction "D1_1") (pintype "input"))
      (node (ref "IC4") (pin "9") (pinfunction "Q1_9") (pintype "input"))
      (node (ref "RAM1") (pin "14") (pinfunction "IO2_14") (pintype "input"))
      (node (ref "RAM2") (pin "14") (pinfunction "IO2_14") (pintype "input"))
      (node (ref "RAM3") (pin "14") (pinfunction "IO2_14") (pintype "input"))
      (node (ref "RAM4") (pin "14") (pinfunction "IO2_14") (pintype "input"))
      (node (ref "RAM5") (pin "14") (pinfunction "IO2_14") (pintype "input"))
      (node (ref "RAM6") (pin "14") (pinfunction "IO2_14") (pintype "input"))
      (node (ref "RAM7") (pin "14") (pinfunction "IO2_14") (pintype "input"))
      (node (ref "RAM8") (pin "14") (pinfunction "IO2_14") (pintype "input"))
    )
    (net (code "38") (name "/IO3") (class "Default")
      (node (ref "EDGE1") (pin "WR") (pinfunction "!WR_WR") (pintype "output"))
      (node (ref "IC1") (pin "2") (pinfunction "D2_2") (pintype "input"))
      (node (ref "IC4") (pin "2") (pinfunction "D2_2") (pintype "input"))
      (node (ref "IC4") (pin "7") (pinfunction "Q2_7") (pintype "input"))
      (node (ref "RAM1") (pin "15") (pinfunction "IO3_15") (pintype "input"))
      (node (ref "RAM2") (pin "15") (pinfunction "IO3_15") (pintype "input"))
      (node (ref "RAM3") (pin "15") (pinfunction "IO3_15") (pintype "input"))
      (node (ref "RAM4") (pin "15") (pinfunction "IO3_15") (pintype "input"))
      (node (ref "RAM5") (pin "15") (pinfunction "IO3_15") (pintype "input"))
      (node (ref "RAM6") (pin "15") (pinfunction "IO3_15") (pintype "input"))
      (node (ref "RAM7") (pin "15") (pinfunction "IO3_15") (pintype "input"))
      (node (ref "RAM8") (pin "15") (pinfunction "IO3_15") (pintype "input"))
    )
    (net (code "39") (name "/IO4") (class "Default")
      (node (ref "EDGE1") (pin "SW2") (pinfunction "SW_SW2") (pintype "input"))
      (node (ref "IC1") (pin "3") (pinfunction "D3_3") (pintype "input"))
      (node (ref "IC4") (pin "3") (pinfunction "D3_3") (pintype "input"))
      (node (ref "IC4") (pin "6") (pinfunction "Q3_6") (pintype "input"))
      (node (ref "RAM1") (pin "17") (pinfunction "IO4_17") (pintype "input"))
      (node (ref "RAM2") (pin "17") (pinfunction "IO4_17") (pintype "input"))
      (node (ref "RAM3") (pin "17") (pinfunction "IO4_17") (pintype "input"))
      (node (ref "RAM4") (pin "17") (pinfunction "IO4_17") (pintype "input"))
      (node (ref "RAM5") (pin "17") (pinfunction "IO4_17") (pintype "input"))
      (node (ref "RAM6") (pin "17") (pinfunction "IO4_17") (pintype "input"))
      (node (ref "RAM7") (pin "17") (pinfunction "IO4_17") (pintype "input"))
      (node (ref "RAM8") (pin "17") (pinfunction "IO4_17") (pintype "input"))
    )
    (net (code "40") (name "/IO5") (class "Default")
      (node (ref "EDGE1") (pin "RD") (pinfunction "!RD_RD") (pintype "output"))
      (node (ref "IC2") (pin "15") (pinfunction "D0_15") (pintype "input"))
      (node (ref "IC6") (pin "10") (pinfunction "Q0_10") (pintype "input"))
      (node (ref "IC6") (pin "15") (pinfunction "D0_15") (pintype "input"))
      (node (ref "RAM1") (pin "18") (pinfunction "IO5_18") (pintype "input"))
      (node (ref "RAM2") (pin "18") (pinfunction "IO5_18") (pintype "input"))
      (node (ref "RAM3") (pin "18") (pinfunction "IO5_18") (pintype "input"))
      (node (ref "RAM4") (pin "18") (pinfunction "IO5_18") (pintype "input"))
      (node (ref "RAM5") (pin "18") (pinfunction "IO5_18") (pintype "input"))
      (node (ref "RAM6") (pin "18") (pinfunction "IO5_18") (pintype "input"))
      (node (ref "RAM7") (pin "18") (pinfunction "IO5_18") (pintype "input"))
      (node (ref "RAM8") (pin "18") (pinfunction "IO5_18") (pintype "input"))
    )
    (net (code "41") (name "/IO6") (class "Default")
      (node (ref "EDGE1") (pin "+12V") (pinfunction "+12V_+12V") (pintype "input"))
      (node (ref "IC2") (pin "1") (pinfunction "D1_1") (pintype "input"))
      (node (ref "IC6") (pin "1") (pinfunction "D1_1") (pintype "input"))
      (node (ref "RAM1") (pin "19") (pinfunction "IO6_19") (pintype "input"))
      (node (ref "RAM2") (pin "19") (pinfunction "IO6_19") (pintype "input"))
      (node (ref "RAM3") (pin "19") (pinfunction "IO6_19") (pintype "input"))
      (node (ref "RAM4") (pin "19") (pinfunction "IO6_19") (pintype "input"))
      (node (ref "RAM5") (pin "19") (pinfunction "IO6_19") (pintype "input"))
      (node (ref "RAM6") (pin "19") (pinfunction "IO6_19") (pintype "input"))
      (node (ref "RAM7") (pin "19") (pinfunction "IO6_19") (pintype "input"))
      (node (ref "RAM8") (pin "19") (pinfunction "IO6_19") (pintype "input"))
    )
    (net (code "42") (name "/IO7") (class "Default")
      (node (ref "EDGE1") (pin "CS1") (pinfunction "!CS1_CS1") (pintype "output"))
      (node (ref "IC2") (pin "2") (pinfunction "D2_2") (pintype "input"))
      (node (ref "IC6") (pin "2") (pinfunction "D2_2") (pintype "input"))
      (node (ref "RAM1") (pin "20") (pinfunction "IO7_20") (pintype "input"))
      (node (ref "RAM2") (pin "20") (pinfunction "IO7_20") (pintype "input"))
      (node (ref "RAM3") (pin "20") (pinfunction "IO7_20") (pintype "input"))
      (node (ref "RAM4") (pin "20") (pinfunction "IO7_20") (pintype "input"))
      (node (ref "RAM5") (pin "20") (pinfunction "IO7_20") (pintype "input"))
      (node (ref "RAM6") (pin "20") (pinfunction "IO7_20") (pintype "input"))
      (node (ref "RAM7") (pin "20") (pinfunction "IO7_20") (pintype "input"))
      (node (ref "RAM8") (pin "20") (pinfunction "IO7_20") (pintype "input"))
    )
    (net (code "43") (name "/IO8") (class "Default")
      (node (ref "EDGE1") (pin "-12V") (pinfunction "-12V_-12V") (pintype "input"))
      (node (ref "IC2") (pin "3") (pinfunction "D3_3") (pintype "input"))
      (node (ref "IC6") (pin "3") (pinfunction "D3_3") (pintype "input"))
      (node (ref "RAM1") (pin "21") (pinfunction "IO8_21") (pintype "input"))
      (node (ref "RAM2") (pin "21") (pinfunction "IO8_21") (pintype "input"))
      (node (ref "RAM3") (pin "21") (pinfunction "IO8_21") (pintype "input"))
      (node (ref "RAM4") (pin "21") (pinfunction "IO8_21") (pintype "input"))
      (node (ref "RAM5") (pin "21") (pinfunction "IO8_21") (pintype "input"))
      (node (ref "RAM6") (pin "21") (pinfunction "IO8_21") (pintype "input"))
      (node (ref "RAM7") (pin "21") (pinfunction "IO8_21") (pintype "input"))
      (node (ref "RAM8") (pin "21") (pinfunction "IO8_21") (pintype "input"))
    )
    (net (code "44") (name "/OE") (class "Default")
      (node (ref "EDGE1") (pin "D6") (pinfunction "D6_D6") (pintype "input"))
      (node (ref "IC7") (pin "4") (pinfunction "2A_4") (pintype "input"))
      (node (ref "RAM1") (pin "24") (pinfunction "OE_24") (pintype "input"))
      (node (ref "RAM2") (pin "24") (pinfunction "OE_24") (pintype "input"))
      (node (ref "RAM3") (pin "24") (pinfunction "OE_24") (pintype "input"))
      (node (ref "RAM4") (pin "24") (pinfunction "OE_24") (pintype "input"))
      (node (ref "RAM5") (pin "24") (pinfunction "OE_24") (pintype "input"))
      (node (ref "RAM6") (pin "24") (pinfunction "OE_24") (pintype "input"))
      (node (ref "RAM7") (pin "24") (pinfunction "OE_24") (pintype "input"))
      (node (ref "RAM8") (pin "24") (pinfunction "OE_24") (pintype "input"))
    )
    (net (code "45") (name "/R1_1") (class "Default")
      (node (ref "IC1") (pin "12") (pinfunction "WE#_12") (pintype "input"))
      (node (ref "IC2") (pin "12") (pinfunction "WE#_12") (pintype "input"))
      (node (ref "IC4") (pin "12") (pinfunction "WE#_12") (pintype "input"))
      (node (ref "IC6") (pin "12") (pinfunction "WE#_12") (pintype "input"))
      (node (ref "IC7") (pin "3") (pinfunction "1Y_3") (pintype "input"))
      (node (ref "R1") (pin "1") (pinfunction "1_1") (pintype "input"))
    )
    (net (code "46") (name "/R1_2") (class "Default")
      (node (ref "IC3") (pin "19") (pinfunction "P=Q#_19") (pintype "input"))
      (node (ref "IC7") (pin "2") (pinfunction "1B_2") (pintype "input"))
      (node (ref "IC7") (pin "5") (pinfunction "2B_5") (pintype "input"))
      (node (ref "R1") (pin "2") (pinfunction "2_2") (pintype "input"))
    )
    (net (code "47") (name "/T17") (class "Default")
      (node (ref "EDGE1") (pin "BUSDIR") (pinfunction "!BUSDIR_BUSDIR") (pintype "input"))
      (node (ref "IC1") (pin "4") (pinfunction "RA1_4") (pintype "input"))
      (node (ref "IC2") (pin "4") (pinfunction "RA1_4") (pintype "input"))
    )
    (net (code "48") (name "/T24") (class "Default")
      (node (ref "EDGE1") (pin "D1") (pinfunction "D1_D1") (pintype "input"))
      (node (ref "IC5") (pin "4") (pinfunction "G#/2A_4") (pintype "input"))
      (node (ref "IC5") (pin "5") (pinfunction "G#/2B_5") (pintype "input"))
    )
    (net (code "49") (name "/WE") (class "Default")
      (node (ref "EDGE1") (pin "A6") (pinfunction "A6_A6") (pintype "output"))
      (node (ref "IC3") (pin "15") (pinfunction "P6_15") (pintype "input"))
      (node (ref "IC7") (pin "1") (pinfunction "1A_1") (pintype "input"))
      (node (ref "RAM1") (pin "29") (pinfunction "WE_29") (pintype "input"))
      (node (ref "RAM2") (pin "29") (pinfunction "WE_29") (pintype "input"))
      (node (ref "RAM3") (pin "29") (pinfunction "WE_29") (pintype "input"))
      (node (ref "RAM4") (pin "29") (pinfunction "WE_29") (pintype "input"))
      (node (ref "RAM5") (pin "29") (pinfunction "WE_29") (pintype "input"))
      (node (ref "RAM6") (pin "29") (pinfunction "WE_29") (pintype "input"))
      (node (ref "RAM7") (pin "29") (pinfunction "WE_29") (pintype "input"))
      (node (ref "RAM8") (pin "29") (pinfunction "WE_29") (pintype "input"))
    )
    (net (code "50") (name "Net-(EDGE1-!CS12)") (class "Default")
      (node (ref "EDGE1") (pin "CS12") (pinfunction "!CS12_CS12") (pintype "output"))
      (node (ref "EDGE1") (pin "SLTSL") (pinfunction "!SLTSL_SLTSL") (pintype "output"))
    )
    (net (code "51") (name "unconnected-(EDGE1-!CS2-PadCS2)") (class "Default")
      (node (ref "EDGE1") (pin "CS2") (pinfunction "!CS2_CS2") (pintype "output+no_connect"))
    )
    (net (code "52") (name "unconnected-(EDGE1-PadA0)") (class "Default")
      (node (ref "EDGE1") (pin "A0") (pinfunction "A0_A0") (pintype "output+no_connect"))
    )
    (net (code "53") (name "unconnected-(EDGE1-PadA1)") (class "Default")
      (node (ref "EDGE1") (pin "A1") (pinfunction "A1_A1") (pintype "output+no_connect"))
    )
    (net (code "54") (name "unconnected-(EDGE1-PadA2)") (class "Default")
      (node (ref "EDGE1") (pin "A2") (pinfunction "A2_A2") (pintype "output+no_connect"))
    )
    (net (code "55") (name "unconnected-(EDGE1-PadA3)") (class "Default")
      (node (ref "EDGE1") (pin "A3") (pinfunction "A3_A3") (pintype "output+no_connect"))
    )
    (net (code "56") (name "unconnected-(EDGE1-PadA4)") (class "Default")
      (node (ref "EDGE1") (pin "A4") (pinfunction "A4_A4") (pintype "output+no_connect"))
    )
    (net (code "57") (name "unconnected-(EDGE1-PadA7)") (class "Default")
      (node (ref "EDGE1") (pin "A7") (pinfunction "A7_A7") (pintype "output+no_connect"))
    )
    (net (code "58") (name "unconnected-(EDGE1-PadD0)") (class "Default")
      (node (ref "EDGE1") (pin "D0") (pinfunction "D0_D0") (pintype "input+no_connect"))
    )
    (net (code "59") (name "unconnected-(EDGE1-PadD2)") (class "Default")
      (node (ref "EDGE1") (pin "D2") (pinfunction "D2_D2") (pintype "input+no_connect"))
    )
    (net (code "60") (name "unconnected-(EDGE1-PadD3)") (class "Default")
      (node (ref "EDGE1") (pin "D3") (pinfunction "D3_D3") (pintype "input+no_connect"))
    )
    (net (code "61") (name "unconnected-(EDGE1-PadD4)") (class "Default")
      (node (ref "EDGE1") (pin "D4") (pinfunction "D4_D4") (pintype "input+no_connect"))
    )
    (net (code "62") (name "unconnected-(EDGE1-PadD5)") (class "Default")
      (node (ref "EDGE1") (pin "D5") (pinfunction "D5_D5") (pintype "input+no_connect"))
    )
    (net (code "63") (name "unconnected-(EDGE1-PadD7)") (class "Default")
      (node (ref "EDGE1") (pin "D7") (pinfunction "D7_D7") (pintype "input+no_connect"))
    )
    (net (code "64") (name "unconnected-(EDGE1-PadSOUNDIN)") (class "Default")
      (node (ref "EDGE1") (pin "SOUNDIN") (pinfunction "SOUNDIN_SOUNDIN") (pintype "input+no_connect"))
    )
    (net (code "65") (name "unconnected-(EDGE1-RES-PadRESV1)") (class "Default")
      (node (ref "EDGE1") (pin "RESV1") (pinfunction "RES_RESV1") (pintype "input+no_connect"))
    )
    (net (code "66") (name "unconnected-(EDGE1-RES-PadRESV2)") (class "Default")
      (node (ref "EDGE1") (pin "RESV2") (pinfunction "RES_RESV2") (pintype "input+no_connect"))
    )
    (net (code "67") (name "unconnected-(IC6-Q1-Pad9)") (class "Default")
      (node (ref "IC6") (pin "9") (pinfunction "Q1_9") (pintype "input+no_connect"))
    )
    (net (code "68") (name "unconnected-(IC6-Q2-Pad7)") (class "Default")
      (node (ref "IC6") (pin "7") (pinfunction "Q2_7") (pintype "input+no_connect"))
    )
    (net (code "69") (name "unconnected-(IC6-Q3-Pad6)") (class "Default")
      (node (ref "IC6") (pin "6") (pinfunction "Q3_6") (pintype "input+no_connect"))
    )
    (net (code "70") (name "unconnected-(IC7-3A-Pad9)") (class "Default")
      (node (ref "IC7") (pin "9") (pinfunction "3A_9") (pintype "input+no_connect"))
    )
    (net (code "71") (name "unconnected-(IC7-3B-Pad10)") (class "Default")
      (node (ref "IC7") (pin "10") (pinfunction "3B_10") (pintype "input+no_connect"))
    )
    (net (code "72") (name "unconnected-(IC7-3Y-Pad8)") (class "Default")
      (node (ref "IC7") (pin "8") (pinfunction "3Y_8") (pintype "input+no_connect"))
    )
    (net (code "73") (name "unconnected-(IC7-4A-Pad12)") (class "Default")
      (node (ref "IC7") (pin "12") (pinfunction "4A_12") (pintype "input+no_connect"))
    )
    (net (code "74") (name "unconnected-(IC7-4B-Pad13)") (class "Default")
      (node (ref "IC7") (pin "13") (pinfunction "4B_13") (pintype "input+no_connect"))
    )
    (net (code "75") (name "unconnected-(IC7-4Y-Pad11)") (class "Default")
      (node (ref "IC7") (pin "11") (pinfunction "4Y_11") (pintype "input+no_connect"))
    )
  )
)
